# 25_LMS3_RX1_BB_ADC.net
KiCad netlist of a schematic drawn in Altium Designer
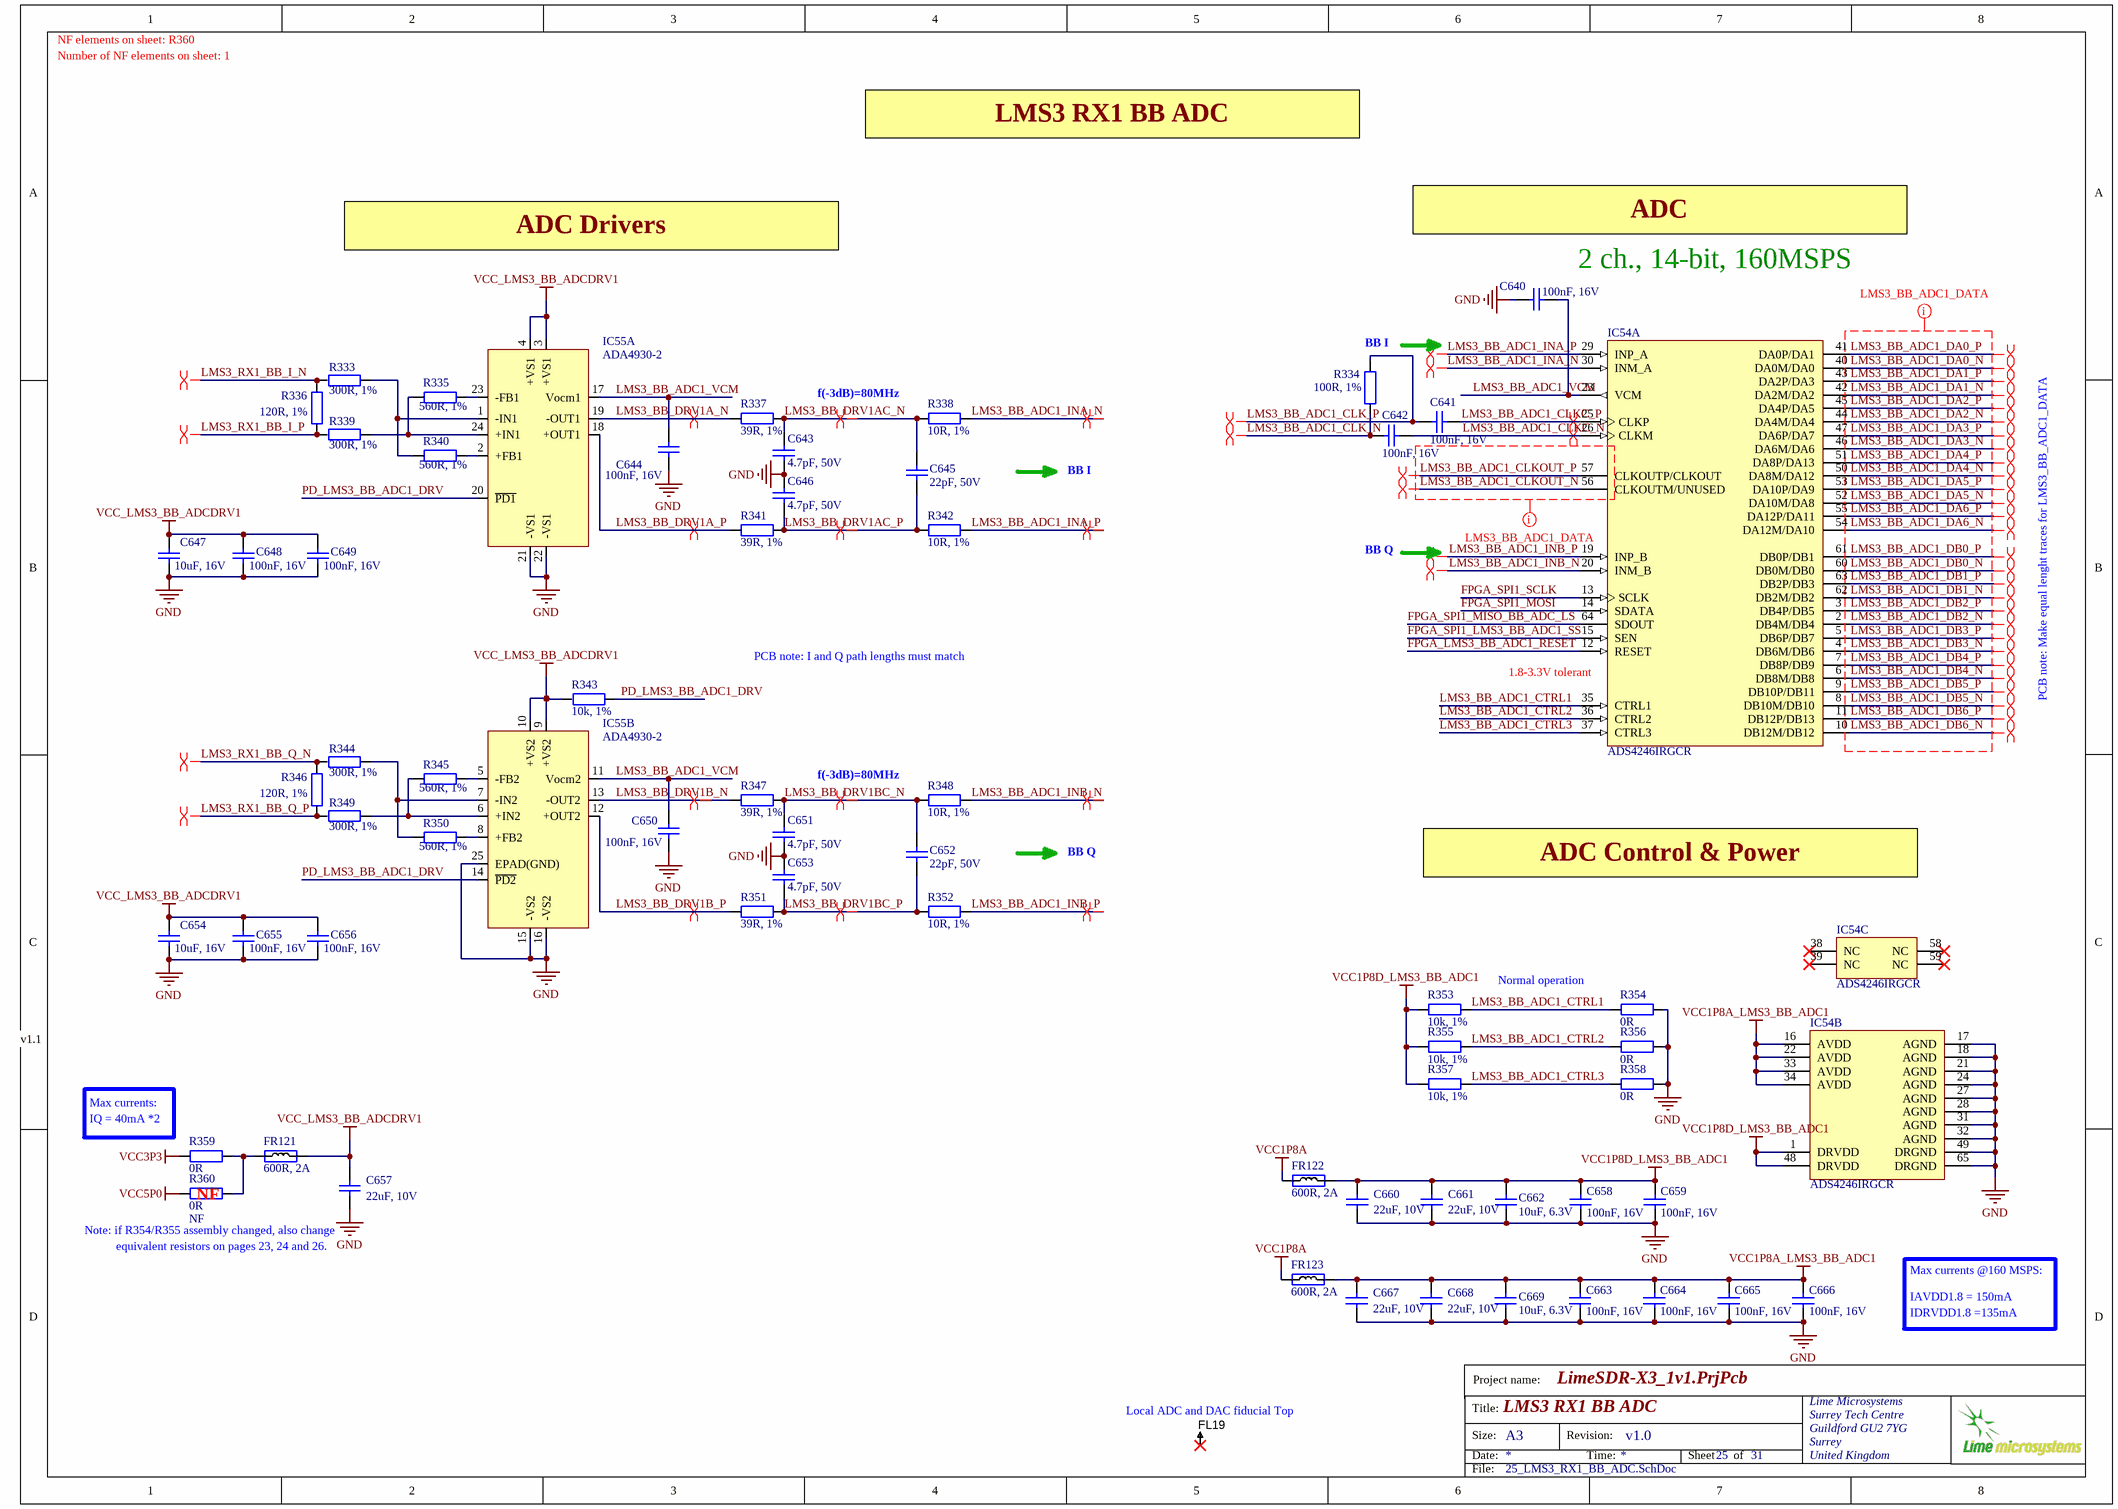
[diagram p0: 25_LMS3_RX1_BB_ADC.SchDoc]

(export (version "E")
  (design (tool "Eeschema 10.0.6"))
  (components
    (comp (ref "C640")
      (value "100nF, 16V")
      (footprint "CAP0402")
      (fields (field (name "TOLERANCE") "10 %") (field (name "MANUFACTURER") "Murata Electronics"))
      (libsource (lib "") (part "Cap_0603_5"))
    )
    (comp (ref "C641")
      (value "100nF, 16V")
      (footprint "CAP0402")
      (fields (field (name "TOLERANCE") "10 %") (field (name "MANUFACTURER") "Murata Electronics"))
      (libsource (lib "") (part "Cap_0603_5"))
    )
    (comp (ref "C642")
      (value "100nF, 16V")
      (footprint "CAP0402")
      (fields (field (name "TOLERANCE") "10 %") (field (name "MANUFACTURER") "Murata Electronics"))
      (libsource (lib "") (part "Cap_0603_1"))
    )
    (comp (ref "C643")
      (value "4.7pF, 50V")
      (footprint "CAP0402")
      (fields (field (name "MANUFACTURER") "MURATA"))
      (libsource (lib "") (part "Cap_0402_1"))
    )
    (comp (ref "C644")
      (value "100nF, 16V")
      (footprint "CAP0402")
      (fields (field (name "TOLERANCE") "10 %") (field (name "MANUFACTURER") "Murata Electronics"))
      (libsource (lib "") (part "Cap_0603_1"))
    )
    (comp (ref "C645")
      (value "22pF, 50V")
      (footprint "CAP0402")
      (fields (field (name "TOLERANCE") "±5%") (field (name "MANUFACTURER") "Yageo"))
      (libsource (lib "LimeMicroAltiumLib_schLib") (part "Cap_0402"))
    )
    (comp (ref "C646")
      (value "4.7pF, 50V")
      (footprint "CAP0402")
      (fields (field (name "MANUFACTURER") "MURATA"))
      (libsource (lib "") (part "Cap_0402_1"))
    )
    (comp (ref "C647")
      (value "10uF, 16V")
      (footprint "CAP0603")
      (fields (field (name "MANUFACTURER") "Yageo") (field (name "TOLERANCE") "±20%"))
      (libsource (lib "LimeMicroAltiumLib_schLib") (part "Cap_0603"))
    )
    (comp (ref "C648")
      (value "100nF, 16V")
      (footprint "CAP0402")
      (fields (field (name "TOLERANCE") "10 %") (field (name "MANUFACTURER") "Murata Electronics"))
      (libsource (lib "") (part "Cap_0603_1"))
    )
    (comp (ref "C649")
      (value "100nF, 16V")
      (footprint "CAP0402")
      (fields (field (name "TOLERANCE") "10 %") (field (name "MANUFACTURER") "Murata Electronics"))
      (libsource (lib "") (part "Cap_0603_1"))
    )
    (comp (ref "C650")
      (value "100nF, 16V")
      (footprint "CAP0402")
      (fields (field (name "TOLERANCE") "10 %") (field (name "MANUFACTURER") "Murata Electronics"))
      (libsource (lib "") (part "Cap_0603_7"))
    )
    (comp (ref "C651")
      (value "4.7pF, 50V")
      (footprint "CAP0402")
      (fields (field (name "MANUFACTURER") "MURATA"))
      (libsource (lib "") (part "Cap_0402_1"))
    )
    (comp (ref "C652")
      (value "22pF, 50V")
      (footprint "CAP0402")
      (fields (field (name "TOLERANCE") "±5%") (field (name "MANUFACTURER") "Yageo"))
      (libsource (lib "LimeMicroAltiumLib_schLib") (part "Cap_0402"))
    )
    (comp (ref "C653")
      (value "4.7pF, 50V")
      (footprint "CAP0402")
      (fields (field (name "MANUFACTURER") "MURATA"))
      (libsource (lib "") (part "Cap_0402_1"))
    )
    (comp (ref "C654")
      (value "10uF, 16V")
      (footprint "CAP0603")
      (fields (field (name "MANUFACTURER") "Yageo") (field (name "TOLERANCE") "±20%"))
      (libsource (lib "LimeMicroAltiumLib_schLib") (part "Cap_0603"))
    )
    (comp (ref "C655")
      (value "100nF, 16V")
      (footprint "CAP0402")
      (fields (field (name "TOLERANCE") "10 %") (field (name "MANUFACTURER") "Murata Electronics"))
      (libsource (lib "") (part "Cap_0603_1"))
    )
    (comp (ref "C656")
      (value "100nF, 16V")
      (footprint "CAP0402")
      (fields (field (name "TOLERANCE") "10 %") (field (name "MANUFACTURER") "Murata Electronics"))
      (libsource (lib "") (part "Cap_0603_1"))
    )
    (comp (ref "C657")
      (value "22uF, 10V")
      (footprint "CAP0603")
      (fields (field (name "TOLERANCE") "20 %") (field (name "MANUFACTURER") "TDK Corporation"))
      (libsource (lib "") (part "Cap_0603_4"))
    )
    (comp (ref "C658")
      (value "100nF, 16V")
      (footprint "CAP0402")
      (fields (field (name "TOLERANCE") "10 %") (field (name "MANUFACTURER") "Murata Electronics"))
      (libsource (lib "LimeFPGAboard_schLib") (part "Cap_0603"))
    )
    (comp (ref "C659")
      (value "100nF, 16V")
      (footprint "CAP0402")
      (fields (field (name "TOLERANCE") "10 %") (field (name "MANUFACTURER") "Murata Electronics"))
      (libsource (lib "LimeFPGAboard_schLib") (part "Cap_0603"))
    )
    (comp (ref "C660")
      (value "22uF, 10V")
      (footprint "CAP0603")
      (fields (field (name "TOLERANCE") "20 %") (field (name "MANUFACTURER") "TDK Corporation"))
      (libsource (lib "LimeFPGAboard_schLib") (part "Cap_0603"))
    )
    (comp (ref "C661")
      (value "22uF, 10V")
      (footprint "CAP0603")
      (fields (field (name "TOLERANCE") "20 %") (field (name "MANUFACTURER") "TDK Corporation"))
      (libsource (lib "LimeFPGAboard_schLib") (part "Cap_0603"))
    )
    (comp (ref "C662")
      (value "10uF, 6.3V")
      (footprint "CAP0603")
      (fields (field (name "TOLERANCE") "±20%") (field (name "MANUFACTURER") "Yageo"))
      (libsource (lib "") (part "Cap_0603_6"))
    )
    (comp (ref "C663")
      (value "100nF, 16V")
      (footprint "CAP0402")
      (fields (field (name "TOLERANCE") "10 %") (field (name "MANUFACTURER") "Murata Electronics"))
      (libsource (lib "") (part "Cap_0603_3"))
    )
    (comp (ref "C664")
      (value "100nF, 16V")
      (footprint "CAP0402")
      (fields (field (name "TOLERANCE") "10 %") (field (name "MANUFACTURER") "Murata Electronics"))
      (libsource (lib "") (part "Cap_0603_3"))
    )
    (comp (ref "C665")
      (value "100nF, 16V")
      (footprint "CAP0402")
      (fields (field (name "TOLERANCE") "10 %") (field (name "MANUFACTURER") "Murata Electronics"))
      (libsource (lib "") (part "Cap_0603_3"))
    )
    (comp (ref "C666")
      (value "100nF, 16V")
      (footprint "CAP0402")
      (fields (field (name "TOLERANCE") "10 %") (field (name "MANUFACTURER") "Murata Electronics"))
      (libsource (lib "") (part "Cap_0603_3"))
    )
    (comp (ref "C667")
      (value "22uF, 10V")
      (footprint "CAP0603")
      (fields (field (name "TOLERANCE") "20 %") (field (name "MANUFACTURER") "TDK Corporation"))
      (libsource (lib "") (part "Cap_0603_3"))
    )
    (comp (ref "C668")
      (value "22uF, 10V")
      (footprint "CAP0603")
      (fields (field (name "TOLERANCE") "20 %") (field (name "MANUFACTURER") "TDK Corporation"))
      (libsource (lib "") (part "Cap_0603_3"))
    )
    (comp (ref "C669")
      (value "10uF, 6.3V")
      (footprint "CAP0603")
      (fields (field (name "TOLERANCE") "±20%") (field (name "MANUFACTURER") "Yageo"))
      (libsource (lib "") (part "Cap_0603_2"))
    )
    (comp (ref "FL19")
      (value "Fiducial")
      (footprint "Fiducial_local")
      (libsource (lib "LimeMicroAltiumLib_schLib") (part "Fiducial"))
    )
    (comp (ref "FR121")
      (value "600R, 2A")
      (footprint "RES0805")
      (fields (field (name "MANUFACTURER") "TDK Corporation"))
      (libsource (lib "LimeMicroAltiumLib_schLib") (part "Ferrite"))
    )
    (comp (ref "FR122")
      (value "600R, 2A")
      (footprint "RES0805")
      (fields (field (name "MANUFACTURER") "TDK Corporation"))
      (libsource (lib "LimeFPGAboard_schLib") (part "Ferrite"))
    )
    (comp (ref "FR123")
      (value "600R, 2A")
      (footprint "RES0805")
      (fields (field (name "MANUFACTURER") "TDK Corporation"))
      (libsource (lib "LimeFPGAboard_schLib") (part "Ferrite"))
    )
    (comp (ref "IC54")
      (value "ADS4246IRGCR")
      (footprint "TI-RGC64-7400X7400TP_V")
      (description "14-Bit 160 MSPS Dual Low Power ADC, -40 to 85 degC, 64-pin QFN (RGC64), Green (RoHS & no Sb/Br)")
      (fields (field (name "MANUFACTURER") "Texas Instruments"))
      (libsource (lib "LimeMicroAltiumLib_schLib") (part "ADS4246IRGCR"))
    )
    (comp (ref "IC55")
      (value "ADA4930-2")
      (footprint "ADA4930-2_LFCSP-24")
      (fields (field (name "MANUFACTURER") "Analog Devices Inc."))
      (libsource (lib "") (part "ADA4930-2_1"))
    )
    (comp (ref "R333")
      (value "300R, 1%")
      (footprint "RES0402")
      (fields (field (name "TOLERANCE") "±1%") (field (name "MANUFACTURER") "Vishay Dale"))
      (libsource (lib "LimeFPGAboard_schLib") (part "Res_0402"))
    )
    (comp (ref "R334")
      (value "100R, 1%")
      (footprint "RES0402")
      (fields (field (name "TOLERANCE") "±1%") (field (name "MANUFACTURER") "Stackpole Electronics Inc."))
      (libsource (lib "LimeFPGAboard_schLib") (part "Res_0402"))
    )
    (comp (ref "R335")
      (value "560R, 1%")
      (footprint "RES0402")
      (fields (field (name "TOLERANCE") "±1%") (field (name "MANUFACTURER") "Vishay Dale"))
      (libsource (lib "LimeFPGAboard_schLib") (part "Res_0402"))
    )
    (comp (ref "R336")
      (value "120R, 1%")
      (footprint "RES0402")
      (fields (field (name "MANUFACTURER") "Yageo") (field (name "TOLERANCE") "1%"))
      (libsource (lib "") (part "Res_0402_1"))
    )
    (comp (ref "R337")
      (value "39R, 1%")
      (footprint "RES0402")
      (fields (field (name "MANUFACTURER") "Yageo") (field (name "TOLERANCE") "1%"))
      (libsource (lib "LimeMicroAltiumLib_schLib") (part "Res_0402"))
    )
    (comp (ref "R338")
      (value "10R, 1%")
      (footprint "RES0402")
      (fields (field (name "TOLERANCE") "1%"))
      (libsource (lib "LimeMicroAltiumLib_schLib") (part "Res_0402"))
    )
    (comp (ref "R339")
      (value "300R, 1%")
      (footprint "RES0402")
      (fields (field (name "TOLERANCE") "±1%") (field (name "MANUFACTURER") "Vishay Dale"))
      (libsource (lib "LimeFPGAboard_schLib") (part "Res_0402"))
    )
    (comp (ref "R340")
      (value "560R, 1%")
      (footprint "RES0402")
      (fields (field (name "TOLERANCE") "±1%") (field (name "MANUFACTURER") "Vishay Dale"))
      (libsource (lib "LimeFPGAboard_schLib") (part "Res_0402"))
    )
    (comp (ref "R341")
      (value "39R, 1%")
      (footprint "RES0402")
      (fields (field (name "MANUFACTURER") "Yageo") (field (name "TOLERANCE") "1%"))
      (libsource (lib "LimeMicroAltiumLib_schLib") (part "Res_0402"))
    )
    (comp (ref "R342")
      (value "10R, 1%")
      (footprint "RES0402")
      (fields (field (name "TOLERANCE") "1%"))
      (libsource (lib "LimeMicroAltiumLib_schLib") (part "Res_0402"))
    )
    (comp (ref "R343")
      (value "10k, 1%")
      (footprint "RES0402")
      (fields (field (name "MANUFACTURER") "Yageo") (field (name "TOLERANCE") "±1%"))
      (libsource (lib "LimeMicroAltiumLib_schLib") (part "Res_0402"))
    )
    (comp (ref "R344")
      (value "300R, 1%")
      (footprint "RES0402")
      (fields (field (name "TOLERANCE") "±1%") (field (name "MANUFACTURER") "Vishay Dale"))
      (libsource (lib "LimeFPGAboard_schLib") (part "Res_0402"))
    )
    (comp (ref "R345")
      (value "560R, 1%")
      (footprint "RES0402")
      (fields (field (name "TOLERANCE") "±1%") (field (name "MANUFACTURER") "Vishay Dale"))
      (libsource (lib "LimeFPGAboard_schLib") (part "Res_0402"))
    )
    (comp (ref "R346")
      (value "120R, 1%")
      (footprint "RES0402")
      (fields (field (name "MANUFACTURER") "Yageo") (field (name "TOLERANCE") "1%"))
      (libsource (lib "") (part "Res_0402_1"))
    )
    (comp (ref "R347")
      (value "39R, 1%")
      (footprint "RES0402")
      (fields (field (name "MANUFACTURER") "Yageo") (field (name "TOLERANCE") "1%"))
      (libsource (lib "LimeMicroAltiumLib_schLib") (part "Res_0402"))
    )
    (comp (ref "R348")
      (value "10R, 1%")
      (footprint "RES0402")
      (fields (field (name "TOLERANCE") "1%"))
      (libsource (lib "LimeMicroAltiumLib_schLib") (part "Res_0402"))
    )
    (comp (ref "R349")
      (value "300R, 1%")
      (footprint "RES0402")
      (fields (field (name "TOLERANCE") "±1%") (field (name "MANUFACTURER") "Vishay Dale"))
      (libsource (lib "LimeFPGAboard_schLib") (part "Res_0402"))
    )
    (comp (ref "R350")
      (value "560R, 1%")
      (footprint "RES0402")
      (fields (field (name "TOLERANCE") "±1%") (field (name "MANUFACTURER") "Vishay Dale"))
      (libsource (lib "LimeFPGAboard_schLib") (part "Res_0402"))
    )
    (comp (ref "R351")
      (value "39R, 1%")
      (footprint "RES0402")
      (fields (field (name "MANUFACTURER") "Yageo") (field (name "TOLERANCE") "1%"))
      (libsource (lib "LimeMicroAltiumLib_schLib") (part "Res_0402"))
    )
    (comp (ref "R352")
      (value "10R, 1%")
      (footprint "RES0402")
      (fields (field (name "TOLERANCE") "1%"))
      (libsource (lib "LimeMicroAltiumLib_schLib") (part "Res_0402"))
    )
    (comp (ref "R353")
      (value "10k, 1%")
      (footprint "RES0402")
      (fields (field (name "MANUFACTURER") "Yageo") (field (name "TOLERANCE") "±1%"))
      (libsource (lib "LimeMicroAltiumLib_schLib") (part "Res_0402"))
    )
    (comp (ref "R354")
      (value "0R")
      (footprint "RES0402")
      (fields (field (name "MANUFACTURER") "Yageo"))
      (libsource (lib "LimeFPGAboard_schLib") (part "Res_0402"))
    )
    (comp (ref "R355")
      (value "10k, 1%")
      (footprint "RES0402")
      (fields (field (name "MANUFACTURER") "Yageo") (field (name "TOLERANCE") "±1%"))
      (libsource (lib "LimeMicroAltiumLib_schLib") (part "Res_0402"))
    )
    (comp (ref "R356")
      (value "0R")
      (footprint "RES0402")
      (fields (field (name "MANUFACTURER") "Yageo"))
      (libsource (lib "LimeFPGAboard_schLib") (part "Res_0402"))
    )
    (comp (ref "R357")
      (value "10k, 1%")
      (footprint "RES0402")
      (fields (field (name "MANUFACTURER") "Yageo") (field (name "TOLERANCE") "±1%"))
      (libsource (lib "LimeMicroAltiumLib_schLib") (part "Res_0402"))
    )
    (comp (ref "R358")
      (value "0R")
      (footprint "RES0402")
      (fields (field (name "MANUFACTURER") "Yageo"))
      (libsource (lib "LimeFPGAboard_schLib") (part "Res_0402"))
    )
    (comp (ref "R359")
      (value "0R")
      (footprint "RES0402")
      (fields (field (name "MANUFACTURER") "Yageo") (field (name "TOLERANCE") "Jumper"))
      (libsource (lib "LimeMicroAltiumLib_schLib") (part "Res_0402"))
    )
    (comp (ref "R360")
      (value "0R")
      (footprint "RES0402")
      (fields
        (field (name "ASSEMBLY INFO") "NF")
        (field (name "MANUFACTURER") "Yageo")
        (field (name "TOLERANCE") "Jumper")
      )
      (libsource (lib "LimeMicroAltiumLib_schLib") (part "Res_0402"))
    )
  )
  (nets
    (net (code "1") (name "/FPGA_LMS3_BB_ADC1_RESET") (class "Default")
      (node (ref "IC54") (pin "12") (pinfunction "RESET_12") (pintype "input"))
    )
    (net (code "2") (name "/FPGA_SPI1_LMS3_BB_ADC1_SS") (class "Default")
      (node (ref "IC54") (pin "15") (pinfunction "SEN_15") (pintype "input"))
    )
    (net (code "3") (name "/FPGA_SPI1_MISO_BB_ADC_LS") (class "Default")
      (node (ref "IC54") (pin "64") (pinfunction "SDOUT_64") (pintype "tri_state"))
    )
    (net (code "4") (name "/FPGA_SPI1_MOSI") (class "Default")
      (node (ref "IC54") (pin "14") (pinfunction "SDATA_14") (pintype "input"))
    )
    (net (code "5") (name "/FPGA_SPI1_SCLK") (class "Default")
      (node (ref "IC54") (pin "13") (pinfunction "SCLK_13") (pintype "input"))
    )
    (net (code "6") (name "/LMS3_BB_ADC1_CLKC_N") (class "Default")
      (node (ref "C642") (pin "1") (pinfunction "1_1") (pintype "passive"))
      (node (ref "IC54") (pin "26") (pinfunction "CLKM_26") (pintype "input"))
    )
    (net (code "7") (name "/LMS3_BB_ADC1_CLKC_P") (class "Default")
      (node (ref "C641") (pin "1") (pinfunction "1_1") (pintype "passive"))
      (node (ref "IC54") (pin "25") (pinfunction "CLKP_25") (pintype "input"))
    )
    (net (code "8") (name "/LMS3_BB_ADC1_CLKOUT_N") (class "Default")
      (node (ref "IC54") (pin "56") (pinfunction "CLKOUTM/UNUSED_56") (pintype "tri_state"))
    )
    (net (code "9") (name "/LMS3_BB_ADC1_CLKOUT_P") (class "Default")
      (node (ref "IC54") (pin "57") (pinfunction "CLKOUTP/CLKOUT_57") (pintype "tri_state"))
    )
    (net (code "10") (name "/LMS3_BB_ADC1_CLK_N") (class "Default")
      (node (ref "C642") (pin "2") (pinfunction "2_2") (pintype "passive"))
      (node (ref "R334") (pin "1") (pinfunction "1_1") (pintype "passive"))
    )
    (net (code "11") (name "/LMS3_BB_ADC1_CLK_P") (class "Default")
      (node (ref "C641") (pin "2") (pinfunction "2_2") (pintype "passive"))
      (node (ref "R334") (pin "2") (pinfunction "2_2") (pintype "passive"))
    )
    (net (code "12") (name "/LMS3_BB_ADC1_CTRL1") (class "Default")
      (node (ref "IC54") (pin "35") (pinfunction "CTRL1_35") (pintype "input"))
      (node (ref "R353") (pin "1") (pinfunction "1_1") (pintype "passive"))
      (node (ref "R354") (pin "2") (pinfunction "2_2") (pintype "passive"))
    )
    (net (code "13") (name "/LMS3_BB_ADC1_CTRL2") (class "Default")
      (node (ref "IC54") (pin "36") (pinfunction "CTRL2_36") (pintype "input"))
      (node (ref "R355") (pin "1") (pinfunction "1_1") (pintype "passive"))
      (node (ref "R356") (pin "2") (pinfunction "2_2") (pintype "passive"))
    )
    (net (code "14") (name "/LMS3_BB_ADC1_CTRL3") (class "Default")
      (node (ref "IC54") (pin "37") (pinfunction "CTRL3_37") (pintype "input"))
      (node (ref "R357") (pin "1") (pinfunction "1_1") (pintype "passive"))
      (node (ref "R358") (pin "2") (pinfunction "2_2") (pintype "passive"))
    )
    (net (code "15") (name "/LMS3_BB_ADC1_DA0_N") (class "Default")
      (node (ref "IC54") (pin "40") (pinfunction "DA0M/DA0_40") (pintype "tri_state"))
    )
    (net (code "16") (name "/LMS3_BB_ADC1_DA0_P") (class "Default")
      (node (ref "IC54") (pin "41") (pinfunction "DA0P/DA1_41") (pintype "tri_state"))
    )
    (net (code "17") (name "/LMS3_BB_ADC1_DA1_N") (class "Default")
      (node (ref "IC54") (pin "42") (pinfunction "DA2M/DA2_42") (pintype "tri_state"))
    )
    (net (code "18") (name "/LMS3_BB_ADC1_DA1_P") (class "Default")
      (node (ref "IC54") (pin "43") (pinfunction "DA2P/DA3_43") (pintype "tri_state"))
    )
    (net (code "19") (name "/LMS3_BB_ADC1_DA2_N") (class "Default")
      (node (ref "IC54") (pin "44") (pinfunction "DA4M/DA4_44") (pintype "tri_state"))
    )
    (net (code "20") (name "/LMS3_BB_ADC1_DA2_P") (class "Default")
      (node (ref "IC54") (pin "45") (pinfunction "DA4P/DA5_45") (pintype "tri_state"))
    )
    (net (code "21") (name "/LMS3_BB_ADC1_DA3_N") (class "Default")
      (node (ref "IC54") (pin "46") (pinfunction "DA6M/DA6_46") (pintype "tri_state"))
    )
    (net (code "22") (name "/LMS3_BB_ADC1_DA3_P") (class "Default")
      (node (ref "IC54") (pin "47") (pinfunction "DA6P/DA7_47") (pintype "tri_state"))
    )
    (net (code "23") (name "/LMS3_BB_ADC1_DA4_N") (class "Default")
      (node (ref "IC54") (pin "50") (pinfunction "DA8M/DA12_50") (pintype "tri_state"))
    )
    (net (code "24") (name "/LMS3_BB_ADC1_DA4_P") (class "Default")
      (node (ref "IC54") (pin "51") (pinfunction "DA8P/DA13_51") (pintype "tri_state"))
    )
    (net (code "25") (name "/LMS3_BB_ADC1_DA5_N") (class "Default")
      (node (ref "IC54") (pin "52") (pinfunction "DA10M/DA8_52") (pintype "tri_state"))
    )
    (net (code "26") (name "/LMS3_BB_ADC1_DA5_P") (class "Default")
      (node (ref "IC54") (pin "53") (pinfunction "DA10P/DA9_53") (pintype "tri_state"))
    )
    (net (code "27") (name "/LMS3_BB_ADC1_DA6_N") (class "Default")
      (node (ref "IC54") (pin "54") (pinfunction "DA12M/DA10_54") (pintype "tri_state"))
    )
    (net (code "28") (name "/LMS3_BB_ADC1_DA6_P") (class "Default")
      (node (ref "IC54") (pin "55") (pinfunction "DA12P/DA11_55") (pintype "tri_state"))
    )
    (net (code "29") (name "/LMS3_BB_ADC1_DB0_N") (class "Default")
      (node (ref "IC54") (pin "60") (pinfunction "DB0M/DB0_60") (pintype "tri_state"))
    )
    (net (code "30") (name "/LMS3_BB_ADC1_DB0_P") (class "Default")
      (node (ref "IC54") (pin "61") (pinfunction "DB0P/DB1_61") (pintype "tri_state"))
    )
    (net (code "31") (name "/LMS3_BB_ADC1_DB1_N") (class "Default")
      (node (ref "IC54") (pin "62") (pinfunction "DB2M/DB2_62") (pintype "tri_state"))
    )
    (net (code "32") (name "/LMS3_BB_ADC1_DB1_P") (class "Default")
      (node (ref "IC54") (pin "63") (pinfunction "DB2P/DB3_63") (pintype "tri_state"))
    )
    (net (code "33") (name "/LMS3_BB_ADC1_DB2_N") (class "Default")
      (node (ref "IC54") (pin "2") (pinfunction "DB4M/DB4_2") (pintype "tri_state"))
    )
    (net (code "34") (name "/LMS3_BB_ADC1_DB2_P") (class "Default")
      (node (ref "IC54") (pin "3") (pinfunction "DB4P/DB5_3") (pintype "tri_state"))
    )
    (net (code "35") (name "/LMS3_BB_ADC1_DB3_N") (class "Default")
      (node (ref "IC54") (pin "4") (pinfunction "DB6M/DB6_4") (pintype "tri_state"))
    )
    (net (code "36") (name "/LMS3_BB_ADC1_DB3_P") (class "Default")
      (node (ref "IC54") (pin "5") (pinfunction "DB6P/DB7_5") (pintype "tri_state"))
    )
    (net (code "37") (name "/LMS3_BB_ADC1_DB4_N") (class "Default")
      (node (ref "IC54") (pin "6") (pinfunction "DB8M/DB8_6") (pintype "tri_state"))
    )
    (net (code "38") (name "/LMS3_BB_ADC1_DB4_P") (class "Default")
      (node (ref "IC54") (pin "7") (pinfunction "DB8P/DB9_7") (pintype "tri_state"))
    )
    (net (code "39") (name "/LMS3_BB_ADC1_DB5_N") (class "Default")
      (node (ref "IC54") (pin "8") (pinfunction "DB10M/DB10_8") (pintype "tri_state"))
    )
    (net (code "40") (name "/LMS3_BB_ADC1_DB5_P") (class "Default")
      (node (ref "IC54") (pin "9") (pinfunction "DB10P/DB11_9") (pintype "tri_state"))
    )
    (net (code "41") (name "/LMS3_BB_ADC1_DB6_N") (class "Default")
      (node (ref "IC54") (pin "10") (pinfunction "DB12M/DB12_10") (pintype "tri_state"))
    )
    (net (code "42") (name "/LMS3_BB_ADC1_DB6_P") (class "Default")
      (node (ref "IC54") (pin "11") (pinfunction "DB12P/DB13_11") (pintype "tri_state"))
    )
    (net (code "43") (name "/LMS3_BB_ADC1_INA_N") (class "Default")
      (node (ref "IC54") (pin "30") (pinfunction "INM_A_30") (pintype "input"))
      (node (ref "R338") (pin "1") (pinfunction "1_1") (pintype "passive"))
    )
    (net (code "44") (name "/LMS3_BB_ADC1_INA_P") (class "Default")
      (node (ref "IC54") (pin "29") (pinfunction "INP_A_29") (pintype "input"))
      (node (ref "R342") (pin "1") (pinfunction "1_1") (pintype "passive"))
    )
    (net (code "45") (name "/LMS3_BB_ADC1_INB_N") (class "Default")
      (node (ref "IC54") (pin "20") (pinfunction "INM_B_20") (pintype "input"))
      (node (ref "R348") (pin "1") (pinfunction "1_1") (pintype "passive"))
    )
    (net (code "46") (name "/LMS3_BB_ADC1_INB_P") (class "Default")
      (node (ref "IC54") (pin "19") (pinfunction "INP_B_19") (pintype "input"))
      (node (ref "R352") (pin "1") (pinfunction "1_1") (pintype "passive"))
    )
    (net (code "47") (name "/LMS3_BB_ADC1_VCM") (class "Default")
      (node (ref "C640") (pin "2") (pinfunction "2_2") (pintype "passive"))
      (node (ref "C644") (pin "1") (pinfunction "1_1") (pintype "passive"))
      (node (ref "C650") (pin "1") (pinfunction "1_1") (pintype "passive"))
      (node (ref "IC54") (pin "23") (pinfunction "VCM_23") (pintype "output"))
      (node (ref "IC55") (pin "11") (pinfunction "Vocm2_11") (pintype "input"))
      (node (ref "IC55") (pin "17") (pinfunction "Vocm1_17") (pintype "input"))
    )
    (net (code "48") (name "/LMS3_BB_DRV1AC_N") (class "Default")
      (node (ref "C643") (pin "1") (pinfunction "1_1") (pintype "passive"))
      (node (ref "C645") (pin "1") (pinfunction "1_1") (pintype "passive"))
      (node (ref "R337") (pin "1") (pinfunction "1_1") (pintype "passive"))
      (node (ref "R338") (pin "2") (pinfunction "2_2") (pintype "passive"))
    )
    (net (code "49") (name "/LMS3_BB_DRV1AC_P") (class "Default")
      (node (ref "C645") (pin "2") (pinfunction "2_2") (pintype "passive"))
      (node (ref "C646") (pin "2") (pinfunction "2_2") (pintype "passive"))
      (node (ref "R341") (pin "1") (pinfunction "1_1") (pintype "passive"))
      (node (ref "R342") (pin "2") (pinfunction "2_2") (pintype "passive"))
    )
    (net (code "50") (name "/LMS3_BB_DRV1A_N") (class "Default")
      (node (ref "IC55") (pin "19") (pinfunction "-OUT1_19") (pintype "output"))
      (node (ref "R337") (pin "2") (pinfunction "2_2") (pintype "passive"))
    )
    (net (code "51") (name "/LMS3_BB_DRV1A_P") (class "Default")
      (node (ref "IC55") (pin "18") (pinfunction "+OUT1_18") (pintype "output"))
      (node (ref "R341") (pin "2") (pinfunction "2_2") (pintype "passive"))
    )
    (net (code "52") (name "/LMS3_BB_DRV1BC_N") (class "Default")
      (node (ref "C651") (pin "1") (pinfunction "1_1") (pintype "passive"))
      (node (ref "C652") (pin "1") (pinfunction "1_1") (pintype "passive"))
      (node (ref "R347") (pin "1") (pinfunction "1_1") (pintype "passive"))
      (node (ref "R348") (pin "2") (pinfunction "2_2") (pintype "passive"))
    )
    (net (code "53") (name "/LMS3_BB_DRV1BC_P") (class "Default")
      (node (ref "C652") (pin "2") (pinfunction "2_2") (pintype "passive"))
      (node (ref "C653") (pin "2") (pinfunction "2_2") (pintype "passive"))
      (node (ref "R351") (pin "1") (pinfunction "1_1") (pintype "passive"))
      (node (ref "R352") (pin "2") (pinfunction "2_2") (pintype "passive"))
    )
    (net (code "54") (name "/LMS3_BB_DRV1B_N") (class "Default")
      (node (ref "IC55") (pin "13") (pinfunction "-OUT2_13") (pintype "output"))
      (node (ref "R347") (pin "2") (pinfunction "2_2") (pintype "passive"))
    )
    (net (code "55") (name "/LMS3_BB_DRV1B_P") (class "Default")
      (node (ref "IC55") (pin "12") (pinfunction "+OUT2_12") (pintype "output"))
      (node (ref "R351") (pin "2") (pinfunction "2_2") (pintype "passive"))
    )
    (net (code "56") (name "/LMS3_RX1_BB_I_N") (class "Default")
      (node (ref "R333") (pin "2") (pinfunction "2_2") (pintype "passive"))
      (node (ref "R336") (pin "2") (pinfunction "2_2") (pintype "passive"))
    )
    (net (code "57") (name "/LMS3_RX1_BB_I_P") (class "Default")
      (node (ref "R336") (pin "1") (pinfunction "1_1") (pintype "passive"))
      (node (ref "R339") (pin "2") (pinfunction "2_2") (pintype "passive"))
    )
    (net (code "58") (name "/LMS3_RX1_BB_Q_N") (class "Default")
      (node (ref "R344") (pin "2") (pinfunction "2_2") (pintype "passive"))
      (node (ref "R346") (pin "2") (pinfunction "2_2") (pintype "passive"))
    )
    (net (code "59") (name "/LMS3_RX1_BB_Q_P") (class "Default")
      (node (ref "R346") (pin "1") (pinfunction "1_1") (pintype "passive"))
      (node (ref "R349") (pin "2") (pinfunction "2_2") (pintype "passive"))
    )
    (net (code "60") (name "/PD_LMS3_BB_ADC1_DRV") (class "Default")
      (node (ref "IC55") (pin "14") (pinfunction "~{PD2}_14") (pintype "input"))
      (node (ref "IC55") (pin "20") (pinfunction "~{PD1}_20") (pintype "input"))
      (node (ref "R343") (pin "1") (pinfunction "1_1") (pintype "passive"))
    )
    (net (code "61") (name "GND") (class "Default")
      (node (ref "C640") (pin "1") (pinfunction "1_1") (pintype "passive"))
      (node (ref "C643") (pin "2") (pinfunction "2_2") (pintype "passive"))
      (node (ref "C644") (pin "2") (pinfunction "2_2") (pintype "passive"))
      (node (ref "C646") (pin "1") (pinfunction "1_1") (pintype "passive"))
      (node (ref "C647") (pin "1") (pinfunction "1_1") (pintype "passive"))
      (node (ref "C648") (pin "2") (pinfunction "2_2") (pintype "passive"))
      (node (ref "C649") (pin "2") (pinfunction "2_2") (pintype "passive"))
      (node (ref "C650") (pin "2") (pinfunction "2_2") (pintype "passive"))
      (node (ref "C651") (pin "2") (pinfunction "2_2") (pintype "passive"))
      (node (ref "C653") (pin "1") (pinfunction "1_1") (pintype "passive"))
      (node (ref "C654") (pin "1") (pinfunction "1_1") (pintype "passive"))
      (node (ref "C655") (pin "2") (pinfunction "2_2") (pintype "passive"))
      (node (ref "C656") (pin "2") (pinfunction "2_2") (pintype "passive"))
      (node (ref "C657") (pin "1") (pinfunction "1_1") (pintype "passive"))
      (node (ref "C658") (pin "1") (pinfunction "1_1") (pintype "passive"))
      (node (ref "C659") (pin "1") (pinfunction "1_1") (pintype "passive"))
      (node (ref "C660") (pin "1") (pinfunction "1_1") (pintype "passive"))
      (node (ref "C661") (pin "1") (pinfunction "1_1") (pintype "passive"))
      (node (ref "C662") (pin "2") (pinfunction "2_2") (pintype "passive"))
      (node (ref "C663") (pin "1") (pinfunction "1_1") (pintype "passive"))
      (node (ref "C664") (pin "1") (pinfunction "1_1") (pintype "passive"))
      (node (ref "C665") (pin "1") (pinfunction "1_1") (pintype "passive"))
      (node (ref "C666") (pin "1") (pinfunction "1_1") (pintype "passive"))
      (node (ref "C667") (pin "1") (pinfunction "1_1") (pintype "passive"))
      (node (ref "C668") (pin "1") (pinfunction "1_1") (pintype "passive"))
      (node (ref "C669") (pin "2") (pinfunction "2_2") (pintype "passive"))
      (node (ref "IC54") (pin "17") (pinfunction "AGND_17") (pintype "power_in"))
      (node (ref "IC54") (pin "18") (pinfunction "AGND_18") (pintype "power_in"))
      (node (ref "IC54") (pin "21") (pinfunction "AGND_21") (pintype "power_in"))
      (node (ref "IC54") (pin "24") (pinfunction "AGND_24") (pintype "power_in"))
      (node (ref "IC54") (pin "27") (pinfunction "AGND_27") (pintype "power_in"))
      (node (ref "IC54") (pin "28") (pinfunction "AGND_28") (pintype "power_in"))
      (node (ref "IC54") (pin "31") (pinfunction "AGND_31") (pintype "power_in"))
      (node (ref "IC54") (pin "32") (pinfunction "AGND_32") (pintype "power_in"))
      (node (ref "IC54") (pin "49") (pinfunction "DRGND_49") (pintype "power_in"))
      (node (ref "IC54") (pin "65") (pinfunction "DRGND_65") (pintype "power_in"))
      (node (ref "IC55") (pin "15") (pinfunction "-VS2_15") (pintype "power_in"))
      (node (ref "IC55") (pin "16") (pinfunction "-VS2_16") (pintype "power_in"))
      (node (ref "IC55") (pin "21") (pinfunction "-VS1_21") (pintype "power_in"))
      (node (ref "IC55") (pin "22") (pinfunction "-VS1_22") (pintype "power_in"))
      (node (ref "IC55") (pin "25") (pinfunction "EPAD(GND)_25") (pintype "passive"))
      (node (ref "R354") (pin "1") (pinfunction "1_1") (pintype "passive"))
      (node (ref "R356") (pin "1") (pinfunction "1_1") (pintype "passive"))
      (node (ref "R358") (pin "1") (pinfunction "1_1") (pintype "passive"))
    )
    (net (code "62") (name "Net-(FR121-Pad1)") (class "Default")
      (node (ref "FR121") (pin "1") (pinfunction "1_1") (pintype "passive"))
      (node (ref "R359") (pin "1") (pinfunction "1_1") (pintype "passive"))
      (node (ref "R360") (pin "1") (pinfunction "1_1") (pintype "passive"))
    )
    (net (code "63") (name "Net-(IC55A-+FB1)") (class "Default")
      (node (ref "IC55") (pin "2") (pinfunction "+FB1_2") (pintype "output"))
      (node (ref "R340") (pin "1") (pinfunction "1_1") (pintype "passive"))
    )
    (net (code "64") (name "Net-(IC55A-+IN1)") (class "Default")
      (node (ref "IC55") (pin "24") (pinfunction "+IN1_24") (pintype "input"))
      (node (ref "R335") (pin "2") (pinfunction "2_2") (pintype "passive"))
      (node (ref "R339") (pin "1") (pinfunction "1_1") (pintype "passive"))
    )
    (net (code "65") (name "Net-(IC55A--FB1)") (class "Default")
      (node (ref "IC55") (pin "23") (pinfunction "-FB1_23") (pintype "output"))
      (node (ref "R335") (pin "1") (pinfunction "1_1") (pintype "passive"))
    )
    (net (code "66") (name "Net-(IC55A--IN1)") (class "Default")
      (node (ref "IC55") (pin "1") (pinfunction "-IN1_1") (pintype "input"))
      (node (ref "R333") (pin "1") (pinfunction "1_1") (pintype "passive"))
      (node (ref "R340") (pin "2") (pinfunction "2_2") (pintype "passive"))
    )
    (net (code "67") (name "Net-(IC55B-+FB2)") (class "Default")
      (node (ref "IC55") (pin "8") (pinfunction "+FB2_8") (pintype "output"))
      (node (ref "R350") (pin "1") (pinfunction "1_1") (pintype "passive"))
    )
    (net (code "68") (name "Net-(IC55B-+IN2)") (class "Default")
      (node (ref "IC55") (pin "6") (pinfunction "+IN2_6") (pintype "input"))
      (node (ref "R345") (pin "2") (pinfunction "2_2") (pintype "passive"))
      (node (ref "R349") (pin "1") (pinfunction "1_1") (pintype "passive"))
    )
    (net (code "69") (name "Net-(IC55B--FB2)") (class "Default")
      (node (ref "IC55") (pin "5") (pinfunction "-FB2_5") (pintype "output"))
      (node (ref "R345") (pin "1") (pinfunction "1_1") (pintype "passive"))
    )
    (net (code "70") (name "Net-(IC55B--IN2)") (class "Default")
      (node (ref "IC55") (pin "7") (pinfunction "-IN2_7") (pintype "input"))
      (node (ref "R344") (pin "1") (pinfunction "1_1") (pintype "passive"))
      (node (ref "R350") (pin "2") (pinfunction "2_2") (pintype "passive"))
    )
    (net (code "71") (name "VCC1P8A") (class "Default")
      (node (ref "FR122") (pin "1") (pinfunction "1_1") (pintype "passive"))
      (node (ref "FR123") (pin "1") (pinfunction "1_1") (pintype "passive"))
    )
    (net (code "72") (name "VCC1P8A_LMS3_BB_ADC1") (class "Default")
      (node (ref "C663") (pin "2") (pinfunction "2_2") (pintype "passive"))
      (node (ref "C664") (pin "2") (pinfunction "2_2") (pintype "passive"))
      (node (ref "C665") (pin "2") (pinfunction "2_2") (pintype "passive"))
      (node (ref "C666") (pin "2") (pinfunction "2_2") (pintype "passive"))
      (node (ref "C667") (pin "2") (pinfunction "2_2") (pintype "passive"))
      (node (ref "C668") (pin "2") (pinfunction "2_2") (pintype "passive"))
      (node (ref "C669") (pin "1") (pinfunction "1_1") (pintype "passive"))
      (node (ref "FR123") (pin "2") (pinfunction "2_2") (pintype "passive"))
      (node (ref "IC54") (pin "16") (pinfunction "AVDD_16") (pintype "power_in"))
      (node (ref "IC54") (pin "22") (pinfunction "AVDD_22") (pintype "power_in"))
      (node (ref "IC54") (pin "33") (pinfunction "AVDD_33") (pintype "power_in"))
      (node (ref "IC54") (pin "34") (pinfunction "AVDD_34") (pintype "power_in"))
    )
    (net (code "73") (name "VCC1P8D_LMS3_BB_ADC1") (class "Default")
      (node (ref "C658") (pin "2") (pinfunction "2_2") (pintype "passive"))
      (node (ref "C659") (pin "2") (pinfunction "2_2") (pintype "passive"))
      (node (ref "C660") (pin "2") (pinfunction "2_2") (pintype "passive"))
      (node (ref "C661") (pin "2") (pinfunction "2_2") (pintype "passive"))
      (node (ref "C662") (pin "1") (pinfunction "1_1") (pintype "passive"))
      (node (ref "FR122") (pin "2") (pinfunction "2_2") (pintype "passive"))
      (node (ref "IC54") (pin "1") (pinfunction "DRVDD_1") (pintype "power_in"))
      (node (ref "IC54") (pin "48") (pinfunction "DRVDD_48") (pintype "power_in"))
      (node (ref "R353") (pin "2") (pinfunction "2_2") (pintype "passive"))
      (node (ref "R355") (pin "2") (pinfunction "2_2") (pintype "passive"))
      (node (ref "R357") (pin "2") (pinfunction "2_2") (pintype "passive"))
    )
    (net (code "74") (name "VCC3P3") (class "Default")
      (node (ref "R359") (pin "2") (pinfunction "2_2") (pintype "passive"))
    )
    (net (code "75") (name "VCC5P0") (class "Default")
      (node (ref "R360") (pin "2") (pinfunction "2_2") (pintype "passive"))
    )
    (net (code "76") (name "VCC_LMS3_BB_ADCDRV1") (class "Default")
      (node (ref "C647") (pin "2") (pinfunction "2_2") (pintype "passive"))
      (node (ref "C648") (pin "1") (pinfunction "1_1") (pintype "passive"))
      (node (ref "C649") (pin "1") (pinfunction "1_1") (pintype "passive"))
      (node (ref "C654") (pin "2") (pinfunction "2_2") (pintype "passive"))
      (node (ref "C655") (pin "1") (pinfunction "1_1") (pintype "passive"))
      (node (ref "C656") (pin "1") (pinfunction "1_1") (pintype "passive"))
      (node (ref "C657") (pin "2") (pinfunction "2_2") (pintype "passive"))
      (node (ref "FR121") (pin "2") (pinfunction "2_2") (pintype "passive"))
      (node (ref "IC55") (pin "10") (pinfunction "+VS2_10") (pintype "power_in"))
      (node (ref "IC55") (pin "3") (pinfunction "+VS1_3") (pintype "power_in"))
      (node (ref "IC55") (pin "4") (pinfunction "+VS1_4") (pintype "power_in"))
      (node (ref "IC55") (pin "9") (pinfunction "+VS2_9") (pintype "power_in"))
      (node (ref "R343") (pin "2") (pinfunction "2_2") (pintype "passive"))
    )
    (net (code "77") (name "unconnected-(FL19-Pad1)") (class "Default")
      (node (ref "FL19") (pin "1") (pintype "passive+no_connect"))
    )
    (net (code "78") (name "unconnected-(IC54C-NC-Pad38)") (class "Default")
      (node (ref "IC54") (pin "38") (pinfunction "NC_38") (pintype "passive+no_connect"))
    )
    (net (code "79") (name "unconnected-(IC54C-NC-Pad39)") (class "Default")
      (node (ref "IC54") (pin "39") (pinfunction "NC_39") (pintype "passive+no_connect"))
    )
    (net (code "80") (name "unconnected-(IC54C-NC-Pad58)") (class "Default")
      (node (ref "IC54") (pin "58") (pinfunction "NC_58") (pintype "passive+no_connect"))
    )
    (net (code "81") (name "unconnected-(IC54C-NC-Pad59)") (class "Default")
      (node (ref "IC54") (pin "59") (pinfunction "NC_59") (pintype "passive+no_connect"))
    )
  )
)
